# SOUND_SEC.net
KiCad netlist of a schematic drawn in Altium Designer
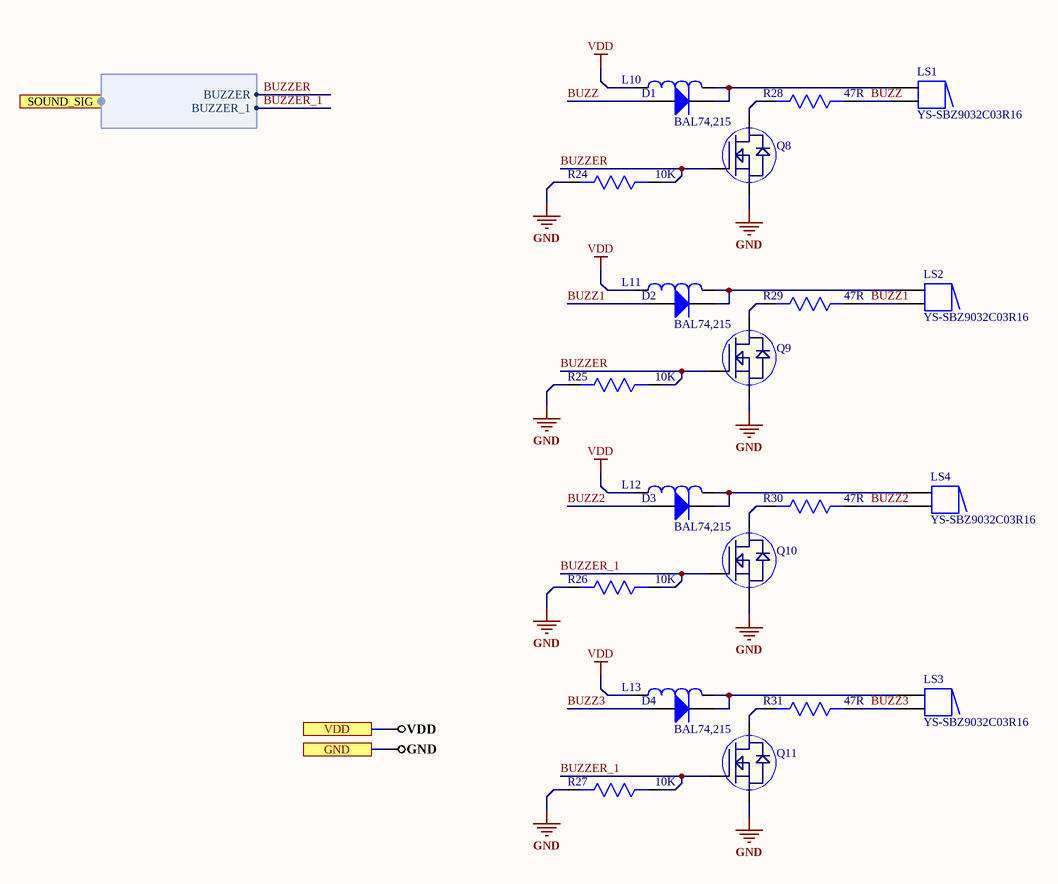
[diagram p0: SOUND_SEC.SchDoc]

(export (version "E")
  (design (tool "Eeschema 10.0.6"))
  (components
    (comp (ref "D1")
      (value "BAL74,215")
      (footprint "SOT23-3")
      (description "DIODE GEN PURP 50V 215MA SOT23")
      (fields
        (field (name "MANUFACTURER") "NXP Semiconductors")
        (field (name "MANUFACTURER PART NUMBER") "BAL74215")
      )
      (libsource (lib "TT_IntLib") (part "BAL74,215"))
    )
    (comp (ref "D2")
      (value "BAL74,215")
      (footprint "SOT23-3")
      (description "DIODE GEN PURP 50V 215MA SOT23")
      (fields
        (field (name "MANUFACTURER") "NXP Semiconductors")
        (field (name "MANUFACTURER PART NUMBER") "BAL74215")
      )
      (libsource (lib "TT_IntLib") (part "BAL74,215"))
    )
    (comp (ref "D3")
      (value "BAL74,215")
      (footprint "SOT23-3")
      (description "DIODE GEN PURP 50V 215MA SOT23")
      (fields
        (field (name "MANUFACTURER") "NXP Semiconductors")
        (field (name "MANUFACTURER PART NUMBER") "BAL74215")
      )
      (libsource (lib "TT_IntLib") (part "BAL74,215"))
    )
    (comp (ref "D4")
      (value "BAL74,215")
      (footprint "SOT23-3")
      (description "DIODE GEN PURP 50V 215MA SOT23")
      (fields
        (field (name "MANUFACTURER") "NXP Semiconductors")
        (field (name "MANUFACTURER PART NUMBER") "BAL74215")
      )
      (libsource (lib "TT_IntLib") (part "BAL74,215"))
    )
    (comp (ref "L10")
      (value "MMZ0603S601CT000")
      (footprint "IND 0201")
      (description "FERRITE BEAD 600 OHM 0201 1LN")
      (fields (field (name "MANUFACTURER") "TDK") (field (name "TOLERANCE") "25%"))
      (libsource (lib "TT_IntLib") (part "MMZ0603S601CT000"))
    )
    (comp (ref "L11")
      (value "MMZ0603S601CT000")
      (footprint "IND 0201")
      (description "FERRITE BEAD 600 OHM 0201 1LN")
      (fields (field (name "MANUFACTURER") "TDK") (field (name "TOLERANCE") "25%"))
      (libsource (lib "TT_IntLib") (part "MMZ0603S601CT000"))
    )
    (comp (ref "L12")
      (value "MMZ0603S601CT000")
      (footprint "IND 0201")
      (description "FERRITE BEAD 600 OHM 0201 1LN")
      (fields (field (name "MANUFACTURER") "TDK") (field (name "TOLERANCE") "25%"))
      (libsource (lib "TT_IntLib") (part "MMZ0603S601CT000"))
    )
    (comp (ref "L13")
      (value "MMZ0603S601CT000")
      (footprint "IND 0201")
      (description "FERRITE BEAD 600 OHM 0201 1LN")
      (fields (field (name "MANUFACTURER") "TDK") (field (name "TOLERANCE") "25%"))
      (libsource (lib "TT_IntLib") (part "MMZ0603S601CT000"))
    )
    (comp (ref "LS1")
      (value "YS-SBZ9032C03R16")
      (footprint "YS-SBZ9032C03R16")
      (description "NO 2700Hz 85dB @ 3V, 10cm 3V Φ9mm SMD,9x3.2mm Buzzers RoHS")
      (fields (field (name "MANUFACTURER") "Fengming"))
      (libsource (lib "TT_IntLib") (part "YS-SBZ9032C03R16"))
    )
    (comp (ref "LS2")
      (value "YS-SBZ9032C03R16")
      (footprint "YS-SBZ9032C03R16")
      (description "NO 2700Hz 85dB @ 3V, 10cm 3V Φ9mm SMD,9x3.2mm Buzzers RoHS")
      (fields (field (name "MANUFACTURER") "Fengming"))
      (libsource (lib "TT_IntLib") (part "YS-SBZ9032C03R16"))
    )
    (comp (ref "LS3")
      (value "YS-SBZ9032C03R16")
      (footprint "YS-SBZ9032C03R16")
      (description "NO 2700Hz 85dB @ 3V, 10cm 3V Φ9mm SMD,9x3.2mm Buzzers RoHS")
      (fields (field (name "MANUFACTURER") "Fengming"))
      (libsource (lib "TT_IntLib") (part "YS-SBZ9032C03R16"))
    )
    (comp (ref "LS4")
      (value "YS-SBZ9032C03R16")
      (footprint "YS-SBZ9032C03R16")
      (description "NO 2700Hz 85dB @ 3V, 10cm 3V Φ9mm SMD,9x3.2mm Buzzers RoHS")
      (fields (field (name "MANUFACTURER") "Fengming"))
      (libsource (lib "TT_IntLib") (part "YS-SBZ9032C03R16"))
    )
    (comp (ref "Q8")
      (value "BSS138LT1G")
      (footprint "SOT23-3")
      (description "MOSFET N-CH 50V 200MA SOT-23")
      (fields (field (name "MANUFACTURER") "ON Semiconductor"))
      (libsource (lib "TT_IntLib") (part "BSS138LT1G"))
    )
    (comp (ref "Q9")
      (value "BSS138LT1G")
      (footprint "SOT23-3")
      (description "MOSFET N-CH 50V 200MA SOT-23")
      (fields (field (name "MANUFACTURER") "ON Semiconductor"))
      (libsource (lib "TT_IntLib") (part "BSS138LT1G"))
    )
    (comp (ref "Q10")
      (value "BSS138LT1G")
      (footprint "SOT23-3")
      (description "MOSFET N-CH 50V 200MA SOT-23")
      (fields (field (name "MANUFACTURER") "ON Semiconductor"))
      (libsource (lib "TT_IntLib") (part "BSS138LT1G"))
    )
    (comp (ref "Q11")
      (value "BSS138LT1G")
      (footprint "SOT23-3")
      (description "MOSFET N-CH 50V 200MA SOT-23")
      (fields (field (name "MANUFACTURER") "ON Semiconductor"))
      (libsource (lib "TT_IntLib") (part "BSS138LT1G"))
    )
    (comp (ref "R24")
      (value "10K")
      (footprint "Res-0201")
      (description "RES SMD 10K OHM 1% 1/20W 0201")
      (fields
        (field (name "MANUFACTURER") "Yageo")
        (field (name "MANUFACTURER PART NUMBER") "RC0201FR-0710KL")
      )
      (libsource (lib "TT_IntLib") (part "RC0201FR-0710KL"))
    )
    (comp (ref "R25")
      (value "10K")
      (footprint "Res-0201")
      (description "RES SMD 10K OHM 1% 1/20W 0201")
      (fields
        (field (name "MANUFACTURER") "Yageo")
        (field (name "MANUFACTURER PART NUMBER") "RC0201FR-0710KL")
      )
      (libsource (lib "TT_IntLib") (part "RC0201FR-0710KL"))
    )
    (comp (ref "R26")
      (value "10K")
      (footprint "Res-0201")
      (description "RES SMD 10K OHM 1% 1/20W 0201")
      (fields
        (field (name "MANUFACTURER") "Yageo")
        (field (name "MANUFACTURER PART NUMBER") "RC0201FR-0710KL")
      )
      (libsource (lib "TT_IntLib") (part "RC0201FR-0710KL"))
    )
    (comp (ref "R27")
      (value "10K")
      (footprint "Res-0201")
      (description "RES SMD 10K OHM 1% 1/20W 0201")
      (fields
        (field (name "MANUFACTURER") "Yageo")
        (field (name "MANUFACTURER PART NUMBER") "RC0201FR-0710KL")
      )
      (libsource (lib "TT_IntLib") (part "RC0201FR-0710KL"))
    )
    (comp (ref "R28")
      (value "47R")
      (footprint "Res-0201")
      (description "RES 47 OHM 1% 1/20W 0201")
      (fields
        (field (name "MANUFACTURER") "KOA Speer")
        (field (name "MANUFACTURER PART NUMBER") "RK73H1HTTC47R0F")
      )
      (libsource (lib "TT_IntLib") (part "RK73H1HTTC47R0F"))
    )
    (comp (ref "R29")
      (value "47R")
      (footprint "Res-0201")
      (description "RES 47 OHM 1% 1/20W 0201")
      (fields
        (field (name "MANUFACTURER") "KOA Speer")
        (field (name "MANUFACTURER PART NUMBER") "RK73H1HTTC47R0F")
      )
      (libsource (lib "TT_IntLib") (part "RK73H1HTTC47R0F"))
    )
    (comp (ref "R30")
      (value "47R")
      (footprint "Res-0201")
      (description "RES 47 OHM 1% 1/20W 0201")
      (fields
        (field (name "MANUFACTURER") "KOA Speer")
        (field (name "MANUFACTURER PART NUMBER") "RK73H1HTTC47R0F")
      )
      (libsource (lib "TT_IntLib") (part "RK73H1HTTC47R0F"))
    )
    (comp (ref "R31")
      (value "47R")
      (footprint "Res-0201")
      (description "RES 47 OHM 1% 1/20W 0201")
      (fields
        (field (name "MANUFACTURER") "KOA Speer")
        (field (name "MANUFACTURER PART NUMBER") "RK73H1HTTC47R0F")
      )
      (libsource (lib "TT_IntLib") (part "RK73H1HTTC47R0F"))
    )
  )
  (nets
    (net (code "2") (name "/BUZZ") (class "Default")
      (node (ref "D1") (pin "2") (pinfunction "A_2") (pintype "passive"))
      (node (ref "LS1") (pin "2") (pinfunction "2_2") (pintype "passive"))
      (node (ref "R28") (pin "1") (pintype "passive"))
    )
    (net (code "3") (name "/BUZZ1") (class "Default")
      (node (ref "D2") (pin "2") (pinfunction "A_2") (pintype "passive"))
      (node (ref "LS2") (pin "2") (pinfunction "2_2") (pintype "passive"))
      (node (ref "R29") (pin "1") (pintype "passive"))
    )
    (net (code "4") (name "/BUZZ2") (class "Default")
      (node (ref "D3") (pin "2") (pinfunction "A_2") (pintype "passive"))
      (node (ref "LS4") (pin "2") (pinfunction "2_2") (pintype "passive"))
      (node (ref "R30") (pin "1") (pintype "passive"))
    )
    (net (code "5") (name "/BUZZ3") (class "Default")
      (node (ref "D4") (pin "2") (pinfunction "A_2") (pintype "passive"))
      (node (ref "LS3") (pin "2") (pinfunction "2_2") (pintype "passive"))
      (node (ref "R31") (pin "1") (pintype "passive"))
    )
    (net (code "6") (name "/BUZZER") (class "Default")
      (node (ref "Q8") (pin "1") (pinfunction "G_1") (pintype "passive"))
      (node (ref "Q9") (pin "1") (pinfunction "G_1") (pintype "passive"))
      (node (ref "R24") (pin "1") (pintype "passive"))
      (node (ref "R25") (pin "1") (pintype "passive"))
    )
    (net (code "7") (name "/BUZZER_1") (class "Default")
      (node (ref "Q10") (pin "1") (pinfunction "G_1") (pintype "passive"))
      (node (ref "Q11") (pin "1") (pinfunction "G_1") (pintype "passive"))
      (node (ref "R26") (pin "1") (pintype "passive"))
      (node (ref "R27") (pin "1") (pintype "passive"))
    )
    (net (code "9") (name "GND") (class "Default")
      (node (ref "Q10") (pin "2") (pinfunction "S_2") (pintype "passive"))
      (node (ref "Q11") (pin "2") (pinfunction "S_2") (pintype "passive"))
      (node (ref "Q8") (pin "2") (pinfunction "S_2") (pintype "passive"))
      (node (ref "Q9") (pin "2") (pinfunction "S_2") (pintype "passive"))
      (node (ref "R24") (pin "2") (pintype "passive"))
      (node (ref "R25") (pin "2") (pintype "passive"))
      (node (ref "R26") (pin "2") (pintype "passive"))
      (node (ref "R27") (pin "2") (pintype "passive"))
    )
    (net (code "10") (name "Net-(D1-K)") (class "Default")
      (node (ref "D1") (pin "1") (pinfunction "K_1") (pintype "passive"))
      (node (ref "L10") (pin "2") (pinfunction "2_2") (pintype "passive"))
      (node (ref "LS1") (pin "1") (pinfunction "1_1") (pintype "passive"))
    )
    (net (code "11") (name "Net-(D2-K)") (class "Default")
      (node (ref "D2") (pin "1") (pinfunction "K_1") (pintype "passive"))
      (node (ref "L11") (pin "2") (pinfunction "2_2") (pintype "passive"))
      (node (ref "LS2") (pin "1") (pinfunction "1_1") (pintype "passive"))
    )
    (net (code "12") (name "Net-(D3-K)") (class "Default")
      (node (ref "D3") (pin "1") (pinfunction "K_1") (pintype "passive"))
      (node (ref "L12") (pin "2") (pinfunction "2_2") (pintype "passive"))
      (node (ref "LS4") (pin "1") (pinfunction "1_1") (pintype "passive"))
    )
    (net (code "13") (name "Net-(D4-K)") (class "Default")
      (node (ref "D4") (pin "1") (pinfunction "K_1") (pintype "passive"))
      (node (ref "L13") (pin "2") (pinfunction "2_2") (pintype "passive"))
      (node (ref "LS3") (pin "1") (pinfunction "1_1") (pintype "passive"))
    )
    (net (code "14") (name "Net-(Q8-D)") (class "Default")
      (node (ref "Q8") (pin "3") (pinfunction "D_3") (pintype "passive"))
      (node (ref "R28") (pin "2") (pintype "passive"))
    )
    (net (code "15") (name "Net-(Q9-D)") (class "Default")
      (node (ref "Q9") (pin "3") (pinfunction "D_3") (pintype "passive"))
      (node (ref "R29") (pin "2") (pintype "passive"))
    )
    (net (code "16") (name "Net-(Q10-D)") (class "Default")
      (node (ref "Q10") (pin "3") (pinfunction "D_3") (pintype "passive"))
      (node (ref "R30") (pin "2") (pintype "passive"))
    )
    (net (code "17") (name "Net-(Q11-D)") (class "Default")
      (node (ref "Q11") (pin "3") (pinfunction "D_3") (pintype "passive"))
      (node (ref "R31") (pin "2") (pintype "passive"))
    )
    (net (code "18") (name "VDD") (class "Default")
      (node (ref "L10") (pin "1") (pinfunction "1_1") (pintype "passive"))
      (node (ref "L11") (pin "1") (pinfunction "1_1") (pintype "passive"))
      (node (ref "L12") (pin "1") (pinfunction "1_1") (pintype "passive"))
      (node (ref "L13") (pin "1") (pinfunction "1_1") (pintype "passive"))
    )
  )
)
